# Wand.net
KiCad netlist of a schematic drawn in Altium Designer
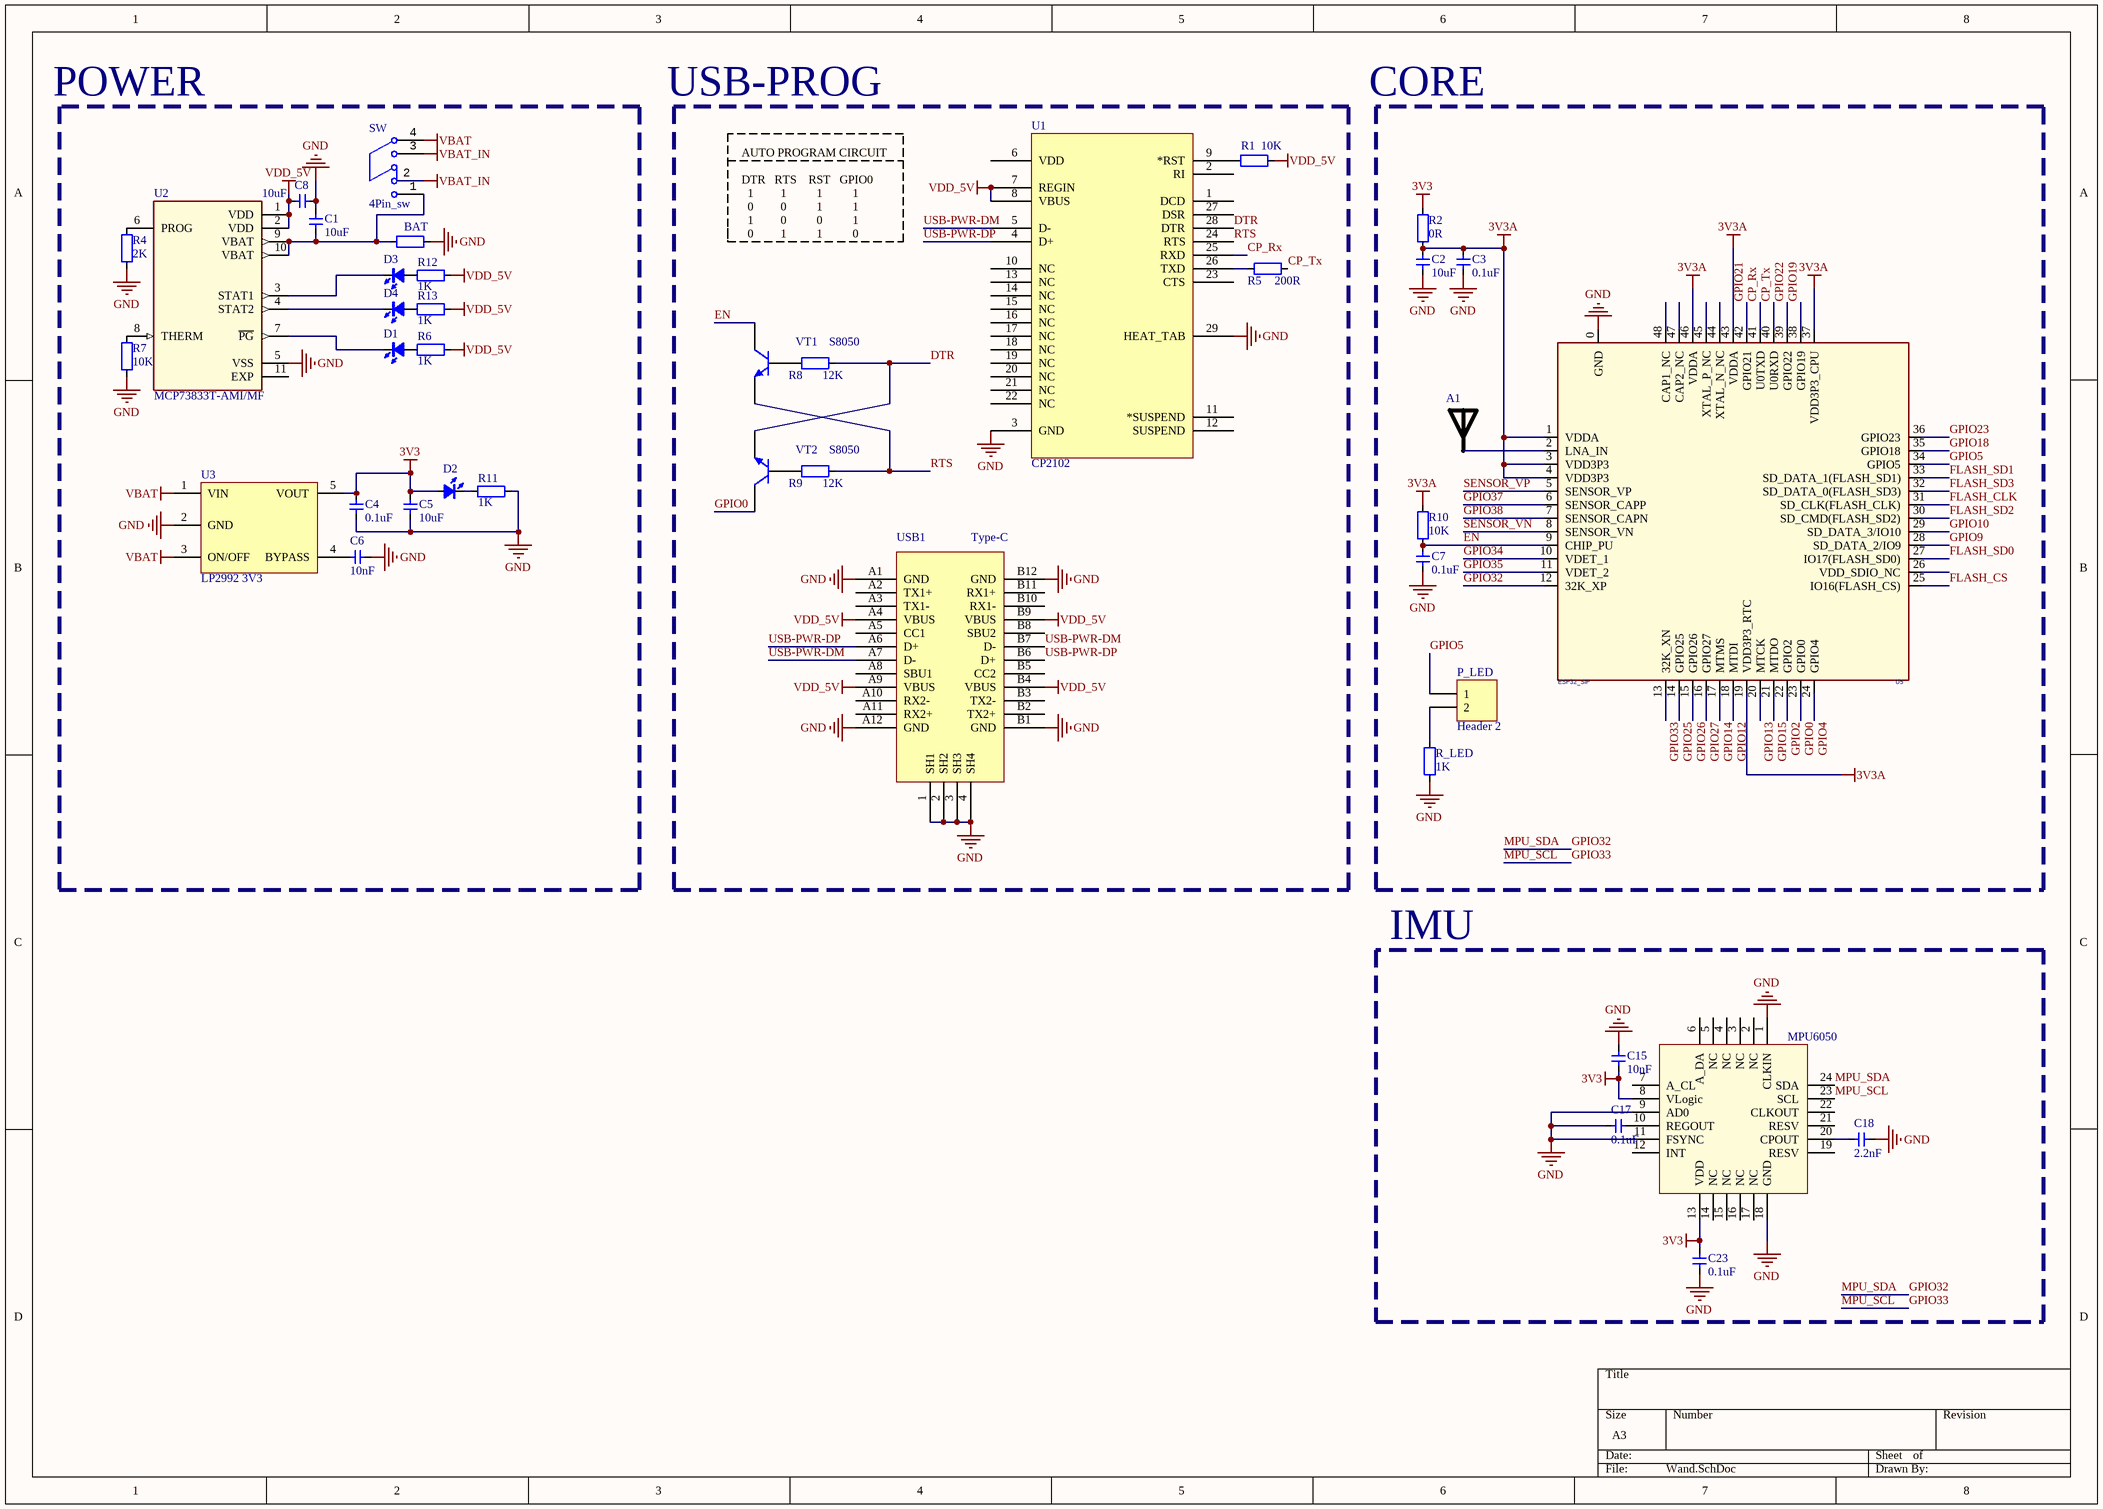
[diagram p0: Wand.SchDoc]

(export (version "E")
  (design (tool "Eeschema 10.0.6"))
  (components
    (comp (ref "A1")
      (value "RAINSUN")
      (footprint "ANT-Rainsun-AN5120")
      (libsource (lib "MyPcbLib") (part "ANT-Rainsun-AP5120"))
    )
    (comp (ref "C1")
      (value "10uF")
      (footprint "0603-CAP")
      (description "Capacitor")
      (libsource (lib "MyPcbLib") (part "电容-0603"))
    )
    (comp (ref "C2")
      (value "10uF")
      (footprint "0603-CAP")
      (description "Capacitor")
      (libsource (lib "MyPcbLib") (part "电容-0603"))
    )
    (comp (ref "C3")
      (value "0.1uF")
      (footprint "CAP_0402")
      (description "Capacitor")
      (libsource (lib "MyPcbLib") (part "电容-0402"))
    )
    (comp (ref "C4")
      (value "0.1uF")
      (footprint "CAP_0402")
      (description "Capacitor")
      (libsource (lib "MyPcbLib") (part "电容-0402"))
    )
    (comp (ref "C5")
      (value "10uF")
      (footprint "0603-CAP")
      (description "Capacitor")
      (libsource (lib "MyPcbLib") (part "电容-0603"))
    )
    (comp (ref "C6")
      (value "10nF")
      (footprint "CAP_0402")
      (description "Capacitor")
      (libsource (lib "MyPcbLib") (part "电容-0402"))
    )
    (comp (ref "C7")
      (value "0.1uF")
      (footprint "CAP_0402")
      (description "Capacitor")
      (libsource (lib "MyPcbLib") (part "电容-0402"))
    )
    (comp (ref "C8")
      (value "10uF")
      (footprint "0603-CAP")
      (description "Capacitor")
      (libsource (lib "MyPcbLib") (part "电容-0603"))
    )
    (comp (ref "C15")
      (value "10nF")
      (footprint "CAP_0402")
      (description "Capacitor")
      (libsource (lib "MyPcbLib") (part "电容-0402"))
    )
    (comp (ref "C17")
      (value "0.1uF")
      (footprint "CAP_0402")
      (description "Capacitor")
      (libsource (lib "MyPcbLib") (part "电容-0402"))
    )
    (comp (ref "C18")
      (value "2.2nF")
      (footprint "CAP_0402")
      (description "Capacitor")
      (libsource (lib "MyPcbLib") (part "电容-0402"))
    )
    (comp (ref "C23")
      (value "0.1uF")
      (footprint "CAP_0402")
      (description "Capacitor")
      (libsource (lib "MyPcbLib") (part "电容-0402"))
    )
    (comp (ref "D1")
      (value "color?")
      (footprint "LED_0402_RED")
      (description "LED")
      (libsource (lib "KitSprout") (part "LED_0402"))
    )
    (comp (ref "D2")
      (value "color?")
      (footprint "LED_0402_RED")
      (description "LED")
      (libsource (lib "") (part "LED_0402_1"))
    )
    (comp (ref "D3")
      (value "color?")
      (footprint "LED_0402_RED")
      (description "LED")
      (libsource (lib "KitSprout") (part "LED_0402"))
    )
    (comp (ref "D4")
      (value "color?")
      (footprint "LED_0402_RED")
      (description "LED")
      (libsource (lib "KitSprout") (part "LED_0402"))
    )
    (comp (ref "P_LED")
      (value "Header 2")
      (footprint "HDR1X2")
      (description "Header, 2-Pin")
      (fields (field (name "PUBLISHER") "Altium Limited"))
      (libsource (lib "Miscellaneous Connectors") (part "Header 2"))
    )
    (comp (ref "R1")
      (value "10K")
      (footprint "RES_0402")
      (description "Resistor")
      (libsource (lib "MyPcbLib") (part "电阻-0402"))
    )
    (comp (ref "R2")
      (value "0R")
      (footprint "RES_0402")
      (description "Resistor")
      (libsource (lib "") (part "电阻-0402_2"))
    )
    (comp (ref "R3")
      (value "BAT")
      (footprint "0805-L")
      (description "Resistor")
      (libsource (lib "MyPcbLib") (part "电阻-0805"))
    )
    (comp (ref "R4")
      (value "2K")
      (footprint "RES_0402")
      (description "Resistor")
      (libsource (lib "") (part "电阻-0402_1"))
    )
    (comp (ref "R5")
      (value "200R")
      (footprint "RES_0402")
      (description "Resistor")
      (libsource (lib "MyPcbLib") (part "电阻-0402"))
    )
    (comp (ref "R6")
      (value "1K")
      (footprint "RES_0402")
      (description "Resistor")
      (libsource (lib "MyPcbLib") (part "电阻-0402"))
    )
    (comp (ref "R7")
      (value "10K")
      (footprint "RES_0402")
      (description "Resistor")
      (libsource (lib "") (part "电阻-0402_1"))
    )
    (comp (ref "R8")
      (value "12K")
      (footprint "RES_0402")
      (description "Resistor")
      (libsource (lib "MyPcbLib") (part "电阻-0402"))
    )
    (comp (ref "R9")
      (value "12K")
      (footprint "RES_0402")
      (description "Resistor")
      (libsource (lib "MyPcbLib") (part "电阻-0402"))
    )
    (comp (ref "R10")
      (value "10K")
      (footprint "RES_0402")
      (description "Resistor")
      (libsource (lib "") (part "电阻-0402_2"))
    )
    (comp (ref "R11")
      (value "1K")
      (footprint "RES_0402")
      (description "Resistor")
      (libsource (lib "MyPcbLib") (part "电阻-0402"))
    )
    (comp (ref "R12")
      (value "1K")
      (footprint "RES_0402")
      (description "Resistor")
      (libsource (lib "MyPcbLib") (part "电阻-0402"))
    )
    (comp (ref "R13")
      (value "1K")
      (footprint "RES_0402")
      (description "Resistor")
      (libsource (lib "MyPcbLib") (part "电阻-0402"))
    )
    (comp (ref "R_LED")
      (value "1K")
      (footprint "RES_0402")
      (description "Resistor")
      (libsource (lib "") (part "电阻-0402_2"))
    )
    (comp (ref "SW") (value "4Pin_sw") (footprint "4pin_SW") (libsource (lib "未分类IC") (part "4Pin_sw")))
    (comp (ref "U1")
      (value "CP2102")
      (footprint "QFN-28")
      (description "USB转TTL")
      (libsource (lib "mLib") (part "CP2102"))
    )
    (comp (ref "U2")
      (value "MCP73833T-AMI/MF")
      (footprint "QFN_10_L")
      (description "Linear Charge Management Controller Li-Ion/Li-Pol 1mA 4.2V/4.35V/4.4V/4.5V 10-Pin DFN EP T/R")
      (fields (field (name "MF") "Microchip"))
      (libsource (lib "mLib") (part "MCP73833T"))
    )
    (comp (ref "U3")
      (value "LP2992 3V3")
      (footprint "SOT23-5")
      (description "LDO")
      (libsource (lib "MyPcbLib") (part "LP2992"))
    )
    (comp (ref "U5")
      (value "ESP32_SIP")
      (footprint "QFN-48_7X7")
      (libsource (lib "MyPcbLib") (part "ESP32-PICO"))
    )
    (comp (ref "U8")
      (value "MPU6050")
      (footprint "QFN-24")
      (description "六轴传感器")
      (libsource (lib "mLib") (part "MPU6050"))
    )
    (comp (ref "USB1")
      (value "Type-C")
      (footprint "Type-C-TOP")
      (libsource (lib "MyPcbLib") (part "USB-Type-C-TOP"))
    )
    (comp (ref "VT1")
      (value "S8050")
      (footprint "SMT_TRIODE_NPN")
      (description "Surface mount NPN transistor, package SOT-23")
      (libsource (lib "MyPcbLib") (part "SMT_TRIODE_NPN"))
    )
    (comp (ref "VT2")
      (value "S8050")
      (footprint "SMT_TRIODE_NPN")
      (description "Surface mount NPN transistor, package SOT-23")
      (libsource (lib "MyPcbLib") (part "SMT_TRIODE_NPN"))
    )
  )
  (nets
    (net (code "1") (name "/CP_Rx") (class "Default")
      (node (ref "U1") (pin "25") (pinfunction "RXD_25") (pintype "passive"))
      (node (ref "U5") (pin "41") (pinfunction "U0TXD_41") (pintype "power_in"))
    )
    (net (code "2") (name "/CP_Tx") (class "Default")
      (node (ref "R5") (pin "1") (pinfunction "1_1") (pintype "passive"))
      (node (ref "U5") (pin "40") (pinfunction "U0RXD_40") (pintype "power_in"))
    )
    (net (code "3") (name "/DTR") (class "Default")
      (node (ref "R8") (pin "1") (pinfunction "1_1") (pintype "passive"))
      (node (ref "U1") (pin "28") (pinfunction "DTR_28") (pintype "passive"))
      (node (ref "VT2") (pin "2") (pinfunction "E_2") (pintype "passive"))
    )
    (net (code "4") (name "/EN") (class "Default")
      (node (ref "C7") (pin "1") (pinfunction "1_1") (pintype "passive"))
      (node (ref "R10") (pin "2") (pinfunction "2_2") (pintype "passive"))
      (node (ref "U5") (pin "9") (pinfunction "CHIP_PU_9") (pintype "passive"))
      (node (ref "VT1") (pin "3") (pinfunction "C_3") (pintype "passive"))
    )
    (net (code "5") (name "/FLASH_CLK") (class "Default")
      (node (ref "U5") (pin "31") (pinfunction "SD_CLK(FLASH_CLK)_31") (pintype "passive"))
    )
    (net (code "6") (name "/FLASH_CS") (class "Default")
      (node (ref "U5") (pin "25") (pinfunction "IO16(FLASH_CS)_25") (pintype "passive"))
    )
    (net (code "7") (name "/FLASH_SD0") (class "Default")
      (node (ref "U5") (pin "27") (pinfunction "IO17(FLASH_SD0)_27") (pintype "passive"))
    )
    (net (code "8") (name "/FLASH_SD1") (class "Default")
      (node (ref "U5") (pin "33") (pinfunction "SD_DATA_1(FLASH_SD1)_33") (pintype "passive"))
    )
    (net (code "9") (name "/FLASH_SD2") (class "Default")
      (node (ref "U5") (pin "30") (pinfunction "SD_CMD(FLASH_SD2)_30") (pintype "passive"))
    )
    (net (code "10") (name "/FLASH_SD3") (class "Default")
      (node (ref "U5") (pin "32") (pinfunction "SD_DATA_0(FLASH_SD3)_32") (pintype "passive"))
    )
    (net (code "11") (name "/GPIO0") (class "Default")
      (node (ref "U5") (pin "23") (pinfunction "GPIO0_23") (pintype "passive"))
      (node (ref "VT2") (pin "3") (pinfunction "C_3") (pintype "passive"))
    )
    (net (code "12") (name "/GPIO2") (class "Default")
      (node (ref "U5") (pin "22") (pinfunction "GPIO2_22") (pintype "passive"))
    )
    (net (code "13") (name "/GPIO4") (class "Default")
      (node (ref "U5") (pin "24") (pinfunction "GPIO4_24") (pintype "passive"))
    )
    (net (code "14") (name "/GPIO5") (class "Default")
      (node (ref "P_LED") (pin "1") (pinfunction "1_1") (pintype "passive"))
      (node (ref "U5") (pin "34") (pinfunction "GPIO5_34") (pintype "passive"))
    )
    (net (code "15") (name "/GPIO9") (class "Default")
      (node (ref "U5") (pin "28") (pinfunction "SD_DATA_2/IO9_28") (pintype "passive"))
    )
    (net (code "16") (name "/GPIO10") (class "Default")
      (node (ref "U5") (pin "29") (pinfunction "SD_DATA_3/IO10_29") (pintype "passive"))
    )
    (net (code "17") (name "/GPIO12") (class "Default")
      (node (ref "U5") (pin "18") (pinfunction "MTDI_18") (pintype "passive"))
    )
    (net (code "18") (name "/GPIO13") (class "Default")
      (node (ref "U5") (pin "20") (pinfunction "MTCK_20") (pintype "passive"))
    )
    (net (code "19") (name "/GPIO14") (class "Default")
      (node (ref "U5") (pin "17") (pinfunction "MTMS_17") (pintype "passive"))
    )
    (net (code "20") (name "/GPIO15") (class "Default")
      (node (ref "U5") (pin "21") (pinfunction "MTDO_21") (pintype "passive"))
    )
    (net (code "21") (name "/GPIO18") (class "Default")
      (node (ref "U5") (pin "35") (pinfunction "GPIO18_35") (pintype "passive"))
    )
    (net (code "22") (name "/GPIO19") (class "Default")
      (node (ref "U5") (pin "38") (pinfunction "GPIO19_38") (pintype "passive"))
    )
    (net (code "23") (name "/GPIO21") (class "Default")
      (node (ref "U5") (pin "42") (pinfunction "GPIO21_42") (pintype "passive"))
    )
    (net (code "24") (name "/GPIO22") (class "Default")
      (node (ref "U5") (pin "39") (pinfunction "GPIO22_39") (pintype "passive"))
    )
    (net (code "25") (name "/GPIO23") (class "Default")
      (node (ref "U5") (pin "36") (pinfunction "GPIO23_36") (pintype "passive"))
    )
    (net (code "26") (name "/GPIO25") (class "Default")
      (node (ref "U5") (pin "14") (pinfunction "GPIO25_14") (pintype "passive"))
    )
    (net (code "27") (name "/GPIO26") (class "Default")
      (node (ref "U5") (pin "15") (pinfunction "GPIO26_15") (pintype "passive"))
    )
    (net (code "28") (name "/GPIO27") (class "Default")
      (node (ref "U5") (pin "16") (pinfunction "GPIO27_16") (pintype "passive"))
    )
    (net (code "29") (name "/GPIO32") (class "Default")
      (node (ref "U5") (pin "12") (pinfunction "32K_XP_12") (pintype "passive"))
      (node (ref "U8") (pin "24") (pinfunction "SDA_24") (pintype "passive"))
    )
    (net (code "30") (name "/GPIO33") (class "Default")
      (node (ref "U5") (pin "13") (pinfunction "32K_XN_13") (pintype "passive"))
      (node (ref "U8") (pin "23") (pinfunction "SCL_23") (pintype "passive"))
    )
    (net (code "31") (name "/GPIO34") (class "Default")
      (node (ref "U5") (pin "10") (pinfunction "VDET_1_10") (pintype "passive"))
    )
    (net (code "32") (name "/GPIO35") (class "Default")
      (node (ref "U5") (pin "11") (pinfunction "VDET_2_11") (pintype "passive"))
    )
    (net (code "33") (name "/GPIO37") (class "Default")
      (node (ref "U5") (pin "6") (pinfunction "SENSOR_CAPP_6") (pintype "passive"))
    )
    (net (code "34") (name "/GPIO38") (class "Default")
      (node (ref "U5") (pin "7") (pinfunction "SENSOR_CAPN_7") (pintype "passive"))
    )
    (net (code "35") (name "/RTS") (class "Default")
      (node (ref "R9") (pin "1") (pinfunction "1_1") (pintype "passive"))
      (node (ref "U1") (pin "24") (pinfunction "RTS_24") (pintype "passive"))
      (node (ref "VT1") (pin "2") (pinfunction "E_2") (pintype "passive"))
    )
    (net (code "36") (name "/SENSOR_VN") (class "Default")
      (node (ref "U5") (pin "8") (pinfunction "SENSOR_VN_8") (pintype "passive"))
    )
    (net (code "37") (name "/SENSOR_VP") (class "Default")
      (node (ref "U5") (pin "5") (pinfunction "SENSOR_VP_5") (pintype "passive"))
    )
    (net (code "38") (name "/USB-PWR-DM") (class "Default")
      (node (ref "U1") (pin "5") (pinfunction "D-_5") (pintype "passive"))
      (node (ref "USB1") (pin "A7") (pinfunction "D-_A7") (pintype "passive"))
      (node (ref "USB1") (pin "B7") (pinfunction "D-_B7") (pintype "passive"))
    )
    (net (code "39") (name "/USB-PWR-DP") (class "Default")
      (node (ref "U1") (pin "4") (pinfunction "D+_4") (pintype "passive"))
      (node (ref "USB1") (pin "A6") (pinfunction "D+_A6") (pintype "passive"))
      (node (ref "USB1") (pin "B6") (pinfunction "D+_B6") (pintype "passive"))
    )
    (net (code "40") (name "3V3") (class "Default")
      (node (ref "C15") (pin "1") (pinfunction "1_1") (pintype "passive"))
      (node (ref "C23") (pin "2") (pinfunction "2_2") (pintype "passive"))
      (node (ref "C4") (pin "2") (pinfunction "2_2") (pintype "passive"))
      (node (ref "C5") (pin "2") (pinfunction "2_2") (pintype "passive"))
      (node (ref "D2") (pin "1") (pinfunction "A_1") (pintype "passive"))
      (node (ref "R2") (pin "1") (pinfunction "1_1") (pintype "passive"))
      (node (ref "U3") (pin "5") (pinfunction "VOUT_5") (pintype "passive"))
      (node (ref "U8") (pin "13") (pinfunction "VDD_13") (pintype "passive"))
      (node (ref "U8") (pin "8") (pinfunction "VLogic_8") (pintype "passive"))
    )
    (net (code "41") (name "3V3A") (class "Default")
      (node (ref "C2") (pin "2") (pinfunction "2_2") (pintype "passive"))
      (node (ref "C3") (pin "2") (pinfunction "2_2") (pintype "passive"))
      (node (ref "R10") (pin "1") (pinfunction "1_1") (pintype "passive"))
      (node (ref "R2") (pin "2") (pinfunction "2_2") (pintype "passive"))
      (node (ref "U5") (pin "1") (pinfunction "VDDA_1") (pintype "power_in"))
      (node (ref "U5") (pin "19") (pinfunction "VDD3P3_RTC_19") (pintype "power_in"))
      (node (ref "U5") (pin "3") (pinfunction "VDD3P3_3") (pintype "power_in"))
      (node (ref "U5") (pin "37") (pinfunction "VDD3P3_CPU_37") (pintype "power_in"))
      (node (ref "U5") (pin "4") (pinfunction "VDD3P3_4") (pintype "power_in"))
      (node (ref "U5") (pin "43") (pinfunction "VDDA_43") (pintype "power_in"))
      (node (ref "U5") (pin "46") (pinfunction "VDDA_46") (pintype "power_in"))
    )
    (net (code "42") (name "GND") (class "Default")
      (node (ref "C1") (pin "2") (pinfunction "2_2") (pintype "passive"))
      (node (ref "C15") (pin "2") (pinfunction "2_2") (pintype "passive"))
      (node (ref "C17") (pin "2") (pinfunction "2_2") (pintype "passive"))
      (node (ref "C18") (pin "1") (pinfunction "1_1") (pintype "passive"))
      (node (ref "C2") (pin "1") (pinfunction "1_1") (pintype "passive"))
      (node (ref "C23") (pin "1") (pinfunction "1_1") (pintype "passive"))
      (node (ref "C3") (pin "1") (pinfunction "1_1") (pintype "passive"))
      (node (ref "C4") (pin "1") (pinfunction "1_1") (pintype "passive"))
      (node (ref "C5") (pin "1") (pinfunction "1_1") (pintype "passive"))
      (node (ref "C6") (pin "1") (pinfunction "1_1") (pintype "passive"))
      (node (ref "C7") (pin "2") (pinfunction "2_2") (pintype "passive"))
      (node (ref "C8") (pin "1") (pinfunction "1_1") (pintype "passive"))
      (node (ref "R11") (pin "1") (pinfunction "1_1") (pintype "passive"))
      (node (ref "R3") (pin "2") (pinfunction "2_2") (pintype "passive"))
      (node (ref "R4") (pin "1") (pinfunction "1_1") (pintype "passive"))
      (node (ref "R7") (pin "1") (pinfunction "1_1") (pintype "passive"))
      (node (ref "R_LED") (pin "2") (pinfunction "2_2") (pintype "passive"))
      (node (ref "U1") (pin "29") (pinfunction "HEAT_TAB_29") (pintype "passive"))
      (node (ref "U1") (pin "3") (pinfunction "GND_3") (pintype "passive"))
      (node (ref "U2") (pin "5") (pinfunction "VSS_5") (pintype "power_in"))
      (node (ref "U3") (pin "2") (pinfunction "GND_2") (pintype "passive"))
      (node (ref "U5") (pin "0") (pinfunction "GND_0") (pintype "power_in"))
      (node (ref "U8") (pin "1") (pinfunction "CLKIN_1") (pintype "passive"))
      (node (ref "U8") (pin "11") (pinfunction "FSYNC_11") (pintype "passive"))
      (node (ref "U8") (pin "18") (pinfunction "GND_18") (pintype "passive"))
      (node (ref "U8") (pin "9") (pinfunction "AD0_9") (pintype "passive"))
      (node (ref "USB1") (pin "1") (pinfunction "SH1_1") (pintype "passive"))
      (node (ref "USB1") (pin "2") (pinfunction "SH2_2") (pintype "passive"))
      (node (ref "USB1") (pin "3") (pinfunction "SH3_3") (pintype "passive"))
      (node (ref "USB1") (pin "4") (pinfunction "SH4_4") (pintype "passive"))
      (node (ref "USB1") (pin "A1") (pinfunction "GND_A1") (pintype "passive"))
      (node (ref "USB1") (pin "A12") (pinfunction "GND_A12") (pintype "passive"))
      (node (ref "USB1") (pin "B1") (pinfunction "GND_B1") (pintype "passive"))
      (node (ref "USB1") (pin "B12") (pinfunction "GND_B12") (pintype "passive"))
    )
    (net (code "43") (name "Net-(C1-Pad1)") (class "Default")
      (node (ref "C1") (pin "1") (pinfunction "1_1") (pintype "passive"))
      (node (ref "R3") (pin "1") (pinfunction "1_1") (pintype "passive"))
      (node (ref "SW") (pin "1") (pinfunction "1_1") (pintype "passive"))
      (node (ref "U2") (pin "10") (pinfunction "VBAT_10") (pintype "output"))
      (node (ref "U2") (pin "9") (pinfunction "VBAT_9") (pintype "output"))
    )
    (net (code "44") (name "Net-(D1-A)") (class "Default")
      (node (ref "D1") (pin "1") (pinfunction "A_1") (pintype "passive"))
      (node (ref "R6") (pin "2") (pinfunction "2_2") (pintype "passive"))
    )
    (net (code "45") (name "Net-(D1-K)") (class "Default")
      (node (ref "D1") (pin "2") (pinfunction "K_2") (pintype "passive"))
      (node (ref "U2") (pin "7") (pinfunction "~{PG}_7") (pintype "output"))
    )
    (net (code "46") (name "Net-(D2-K)") (class "Default")
      (node (ref "D2") (pin "2") (pinfunction "K_2") (pintype "passive"))
      (node (ref "R11") (pin "2") (pinfunction "2_2") (pintype "passive"))
    )
    (net (code "47") (name "Net-(D3-A)") (class "Default")
      (node (ref "D3") (pin "1") (pinfunction "A_1") (pintype "passive"))
      (node (ref "R12") (pin "2") (pinfunction "2_2") (pintype "passive"))
    )
    (net (code "48") (name "Net-(D3-K)") (class "Default")
      (node (ref "D3") (pin "2") (pinfunction "K_2") (pintype "passive"))
      (node (ref "U2") (pin "3") (pinfunction "STAT1_3") (pintype "output"))
    )
    (net (code "49") (name "Net-(D4-A)") (class "Default")
      (node (ref "D4") (pin "1") (pinfunction "A_1") (pintype "passive"))
      (node (ref "R13") (pin "2") (pinfunction "2_2") (pintype "passive"))
    )
    (net (code "50") (name "Net-(D4-K)") (class "Default")
      (node (ref "D4") (pin "2") (pinfunction "K_2") (pintype "passive"))
      (node (ref "U2") (pin "4") (pinfunction "STAT2_4") (pintype "output"))
    )
    (net (code "51") (name "Net-(P_LED-Pad2)") (class "Default")
      (node (ref "P_LED") (pin "2") (pinfunction "2_2") (pintype "passive"))
      (node (ref "R_LED") (pin "1") (pinfunction "1_1") (pintype "passive"))
    )
    (net (code "52") (name "Net-(U1-*RST)") (class "Default")
      (node (ref "R1") (pin "2") (pinfunction "2_2") (pintype "passive"))
      (node (ref "U1") (pin "9") (pinfunction "*RST_9") (pintype "passive"))
    )
    (net (code "53") (name "Net-(U1-TXD)") (class "Default")
      (node (ref "R5") (pin "2") (pinfunction "2_2") (pintype "passive"))
      (node (ref "U1") (pin "26") (pinfunction "TXD_26") (pintype "passive"))
    )
    (net (code "54") (name "Net-(U2-PROG)") (class "Default")
      (node (ref "R4") (pin "2") (pinfunction "2_2") (pintype "passive"))
      (node (ref "U2") (pin "6") (pinfunction "PROG_6") (pintype "passive"))
    )
    (net (code "55") (name "Net-(U2-THERM)") (class "Default")
      (node (ref "R7") (pin "2") (pinfunction "2_2") (pintype "passive"))
      (node (ref "U2") (pin "8") (pinfunction "THERM_8") (pintype "input"))
    )
    (net (code "56") (name "Net-(U3-BYPASS)") (class "Default")
      (node (ref "C6") (pin "2") (pinfunction "2_2") (pintype "passive"))
      (node (ref "U3") (pin "4") (pinfunction "BYPASS_4") (pintype "passive"))
    )
    (net (code "57") (name "Net-(U5-LNA_IN)") (class "Default")
      (node (ref "A1") (pin "1") (pinfunction "1_1") (pintype "passive"))
      (node (ref "U5") (pin "2") (pinfunction "LNA_IN_2") (pintype "passive"))
    )
    (net (code "58") (name "Net-(U8-CPOUT)") (class "Default")
      (node (ref "C18") (pin "2") (pinfunction "2_2") (pintype "passive"))
      (node (ref "U8") (pin "20") (pinfunction "CPOUT_20") (pintype "passive"))
    )
    (net (code "59") (name "Net-(U8-REGOUT)") (class "Default")
      (node (ref "C17") (pin "1") (pinfunction "1_1") (pintype "passive"))
      (node (ref "U8") (pin "10") (pinfunction "REGOUT_10") (pintype "passive"))
    )
    (net (code "60") (name "Net-(VT1-B)") (class "Default")
      (node (ref "R8") (pin "2") (pinfunction "2_2") (pintype "passive"))
      (node (ref "VT1") (pin "1") (pinfunction "B_1") (pintype "passive"))
    )
    (net (code "61") (name "Net-(VT2-B)") (class "Default")
      (node (ref "R9") (pin "2") (pinfunction "2_2") (pintype "passive"))
      (node (ref "VT2") (pin "1") (pinfunction "B_1") (pintype "passive"))
    )
    (net (code "62") (name "VBAT") (class "Default")
      (node (ref "SW") (pin "4") (pinfunction "4_4") (pintype "passive"))
      (node (ref "U3") (pin "1") (pinfunction "VIN_1") (pintype "passive"))
      (node (ref "U3") (pin "3") (pinfunction "ON/OFF_3") (pintype "passive"))
    )
    (net (code "63") (name "VBAT_IN") (class "Default")
      (node (ref "SW") (pin "2") (pinfunction "2_2") (pintype "passive"))
      (node (ref "SW") (pin "3") (pinfunction "3_3") (pintype "passive"))
    )
    (net (code "64") (name "VDD_5V") (class "Default")
      (node (ref "C8") (pin "2") (pinfunction "2_2") (pintype "passive"))
      (node (ref "R1") (pin "1") (pinfunction "1_1") (pintype "passive"))
      (node (ref "R12") (pin "1") (pinfunction "1_1") (pintype "passive"))
      (node (ref "R13") (pin "1") (pinfunction "1_1") (pintype "passive"))
      (node (ref "R6") (pin "1") (pinfunction "1_1") (pintype "passive"))
      (node (ref "U1") (pin "7") (pinfunction "REGIN_7") (pintype "passive"))
      (node (ref "U1") (pin "8") (pinfunction "VBUS_8") (pintype "passive"))
      (node (ref "U2") (pin "1") (pinfunction "VDD_1") (pintype "power_in"))
      (node (ref "U2") (pin "2") (pinfunction "VDD_2") (pintype "power_in"))
      (node (ref "USB1") (pin "A4") (pinfunction "VBUS_A4") (pintype "passive"))
      (node (ref "USB1") (pin "A9") (pinfunction "VBUS_A9") (pintype "passive"))
      (node (ref "USB1") (pin "B4") (pinfunction "VBUS_B4") (pintype "passive"))
      (node (ref "USB1") (pin "B9") (pinfunction "VBUS_B9") (pintype "passive"))
    )
    (net (code "65") (name "unconnected-(U1-*SUSPEND-Pad11)") (class "Default")
      (node (ref "U1") (pin "11") (pinfunction "*SUSPEND_11") (pintype "passive"))
    )
    (net (code "66") (name "unconnected-(U1-CTS-Pad23)") (class "Default")
      (node (ref "U1") (pin "23") (pinfunction "CTS_23") (pintype "passive"))
    )
    (net (code "67") (name "unconnected-(U1-DCD-Pad1)") (class "Default")
      (node (ref "U1") (pin "1") (pinfunction "DCD_1") (pintype "passive"))
    )
    (net (code "68") (name "unconnected-(U1-DSR-Pad27)") (class "Default")
      (node (ref "U1") (pin "27") (pinfunction "DSR_27") (pintype "passive"))
    )
    (net (code "69") (name "unconnected-(U1-NC-Pad10)") (class "Default")
      (node (ref "U1") (pin "10") (pinfunction "NC_10") (pintype "passive"))
    )
    (net (code "70") (name "unconnected-(U1-NC-Pad13)") (class "Default")
      (node (ref "U1") (pin "13") (pinfunction "NC_13") (pintype "passive"))
    )
    (net (code "71") (name "unconnected-(U1-NC-Pad14)") (class "Default")
      (node (ref "U1") (pin "14") (pinfunction "NC_14") (pintype "passive"))
    )
    (net (code "72") (name "unconnected-(U1-NC-Pad15)") (class "Default")
      (node (ref "U1") (pin "15") (pinfunction "NC_15") (pintype "passive"))
    )
    (net (code "73") (name "unconnected-(U1-NC-Pad16)") (class "Default")
      (node (ref "U1") (pin "16") (pinfunction "NC_16") (pintype "passive"))
    )
    (net (code "74") (name "unconnected-(U1-NC-Pad17)") (class "Default")
      (node (ref "U1") (pin "17") (pinfunction "NC_17") (pintype "passive"))
    )
    (net (code "75") (name "unconnected-(U1-NC-Pad18)") (class "Default")
      (node (ref "U1") (pin "18") (pinfunction "NC_18") (pintype "passive"))
    )
    (net (code "76") (name "unconnected-(U1-NC-Pad19)") (class "Default")
      (node (ref "U1") (pin "19") (pinfunction "NC_19") (pintype "passive"))
    )
    (net (code "77") (name "unconnected-(U1-NC-Pad20)") (class "Default")
      (node (ref "U1") (pin "20") (pinfunction "NC_20") (pintype "passive"))
    )
    (net (code "78") (name "unconnected-(U1-NC-Pad21)") (class "Default")
      (node (ref "U1") (pin "21") (pinfunction "NC_21") (pintype "passive"))
    )
    (net (code "79") (name "unconnected-(U1-NC-Pad22)") (class "Default")
      (node (ref "U1") (pin "22") (pinfunction "NC_22") (pintype "passive"))
    )
    (net (code "80") (name "unconnected-(U1-RI-Pad2)") (class "Default")
      (node (ref "U1") (pin "2") (pinfunction "RI_2") (pintype "passive"))
    )
    (net (code "81") (name "unconnected-(U1-SUSPEND-Pad12)") (class "Default")
      (node (ref "U1") (pin "12") (pinfunction "SUSPEND_12") (pintype "passive"))
    )
    (net (code "82") (name "unconnected-(U1-VDD-Pad6)") (class "Default")
      (node (ref "U1") (pin "6") (pinfunction "VDD_6") (pintype "passive"))
    )
    (net (code "83") (name "unconnected-(U2-EXP-Pad11)") (class "Default")
      (node (ref "U2") (pin "11") (pinfunction "EXP_11") (pintype "passive"))
    )
    (net (code "84") (name "unconnected-(U5-CAP1_NC-Pad48)") (class "Default")
      (node (ref "U5") (pin "48") (pinfunction "CAP1_NC_48") (pintype "passive"))
    )
    (net (code "85") (name "unconnected-(U5-CAP2_NC-Pad47)") (class "Default")
      (node (ref "U5") (pin "47") (pinfunction "CAP2_NC_47") (pintype "passive"))
    )
    (net (code "86") (name "unconnected-(U5-VDD_SDIO_NC-Pad26)") (class "Default")
      (node (ref "U5") (pin "26") (pinfunction "VDD_SDIO_NC_26") (pintype "passive"))
    )
    (net (code "87") (name "unconnected-(U5-XTAL_N_NC-Pad44)") (class "Default")
      (node (ref "U5") (pin "44") (pinfunction "XTAL_N_NC_44") (pintype "passive"))
    )
    (net (code "88") (name "unconnected-(U5-XTAL_P_NC-Pad45)") (class "Default")
      (node (ref "U5") (pin "45") (pinfunction "XTAL_P_NC_45") (pintype "passive"))
    )
    (net (code "89") (name "unconnected-(U8-A_CL-Pad7)") (class "Default")
      (node (ref "U8") (pin "7") (pinfunction "A_CL_7") (pintype "passive"))
    )
    (net (code "90") (name "unconnected-(U8-A_DA-Pad6)") (class "Default")
      (node (ref "U8") (pin "6") (pinfunction "A_DA_6") (pintype "passive"))
    )
    (net (code "91") (name "unconnected-(U8-CLKOUT-Pad22)") (class "Default")
      (node (ref "U8") (pin "22") (pinfunction "CLKOUT_22") (pintype "passive"))
    )
    (net (code "92") (name "unconnected-(U8-INT-Pad12)") (class "Default")
      (node (ref "U8") (pin "12") (pinfunction "INT_12") (pintype "passive"))
    )
    (net (code "93") (name "unconnected-(U8-NC-Pad2)") (class "Default")
      (node (ref "U8") (pin "2") (pinfunction "NC_2") (pintype "passive"))
    )
    (net (code "94") (name "unconnected-(U8-NC-Pad3)") (class "Default")
      (node (ref "U8") (pin "3") (pinfunction "NC_3") (pintype "passive"))
    )
    (net (code "95") (name "unconnected-(U8-NC-Pad4)") (class "Default")
      (node (ref "U8") (pin "4") (pinfunction "NC_4") (pintype "passive"))
    )
    (net (code "96") (name "unconnected-(U8-NC-Pad5)") (class "Default")
      (node (ref "U8") (pin "5") (pinfunction "NC_5") (pintype "passive"))
    )
    (net (code "97") (name "unconnected-(U8-NC-Pad14)") (class "Default")
      (node (ref "U8") (pin "14") (pinfunction "NC_14") (pintype "passive"))
    )
    (net (code "98") (name "unconnected-(U8-NC-Pad15)") (class "Default")
      (node (ref "U8") (pin "15") (pinfunction "NC_15") (pintype "passive"))
    )
    (net (code "99") (name "unconnected-(U8-NC-Pad16)") (class "Default")
      (node (ref "U8") (pin "16") (pinfunction "NC_16") (pintype "passive"))
    )
    (net (code "100") (name "unconnected-(U8-NC-Pad17)") (class "Default")
      (node (ref "U8") (pin "17") (pinfunction "NC_17") (pintype "passive"))
    )
    (net (code "101") (name "unconnected-(U8-RESV-Pad19)") (class "Default")
      (node (ref "U8") (pin "19") (pinfunction "RESV_19") (pintype "passive"))
    )
    (net (code "102") (name "unconnected-(U8-RESV-Pad21)") (class "Default")
      (node (ref "U8") (pin "21") (pinfunction "RESV_21") (pintype "passive"))
    )
    (net (code "103") (name "unconnected-(USB1-CC1-PadA5)") (class "Default")
      (node (ref "USB1") (pin "A5") (pinfunction "CC1_A5") (pintype "passive"))
    )
    (net (code "104") (name "unconnected-(USB1-CC2-PadB5)") (class "Default")
      (node (ref "USB1") (pin "B5") (pinfunction "CC2_B5") (pintype "passive"))
    )
    (net (code "105") (name "unconnected-(USB1-RX1+-PadB11)") (class "Default")
      (node (ref "USB1") (pin "B11") (pinfunction "RX1+_B11") (pintype "passive"))
    )
    (net (code "106") (name "unconnected-(USB1-RX1--PadB10)") (class "Default")
      (node (ref "USB1") (pin "B10") (pinfunction "RX1-_B10") (pintype "passive"))
    )
    (net (code "107") (name "unconnected-(USB1-RX2+-PadA11)") (class "Default")
      (node (ref "USB1") (pin "A11") (pinfunction "RX2+_A11") (pintype "passive"))
    )
    (net (code "108") (name "unconnected-(USB1-RX2--PadA10)") (class "Default")
      (node (ref "USB1") (pin "A10") (pinfunction "RX2-_A10") (pintype "passive"))
    )
    (net (code "109") (name "unconnected-(USB1-SBU1-PadA8)") (class "Default")
      (node (ref "USB1") (pin "A8") (pinfunction "SBU1_A8") (pintype "passive"))
    )
    (net (code "110") (name "unconnected-(USB1-SBU2-PadB8)") (class "Default")
      (node (ref "USB1") (pin "B8") (pinfunction "SBU2_B8") (pintype "passive"))
    )
    (net (code "111") (name "unconnected-(USB1-TX1+-PadA2)") (class "Default")
      (node (ref "USB1") (pin "A2") (pinfunction "TX1+_A2") (pintype "passive"))
    )
    (net (code "112") (name "unconnected-(USB1-TX1--PadA3)") (class "Default")
      (node (ref "USB1") (pin "A3") (pinfunction "TX1-_A3") (pintype "passive"))
    )
    (net (code "113") (name "unconnected-(USB1-TX2+-PadB2)") (class "Default")
      (node (ref "USB1") (pin "B2") (pinfunction "TX2+_B2") (pintype "passive"))
    )
    (net (code "114") (name "unconnected-(USB1-TX2--PadB3)") (class "Default")
      (node (ref "USB1") (pin "B3") (pinfunction "TX2-_B3") (pintype "passive"))
    )
  )
)
